# hot_plate_controller.net
KiCad netlist of a schematic drawn in EAGLE
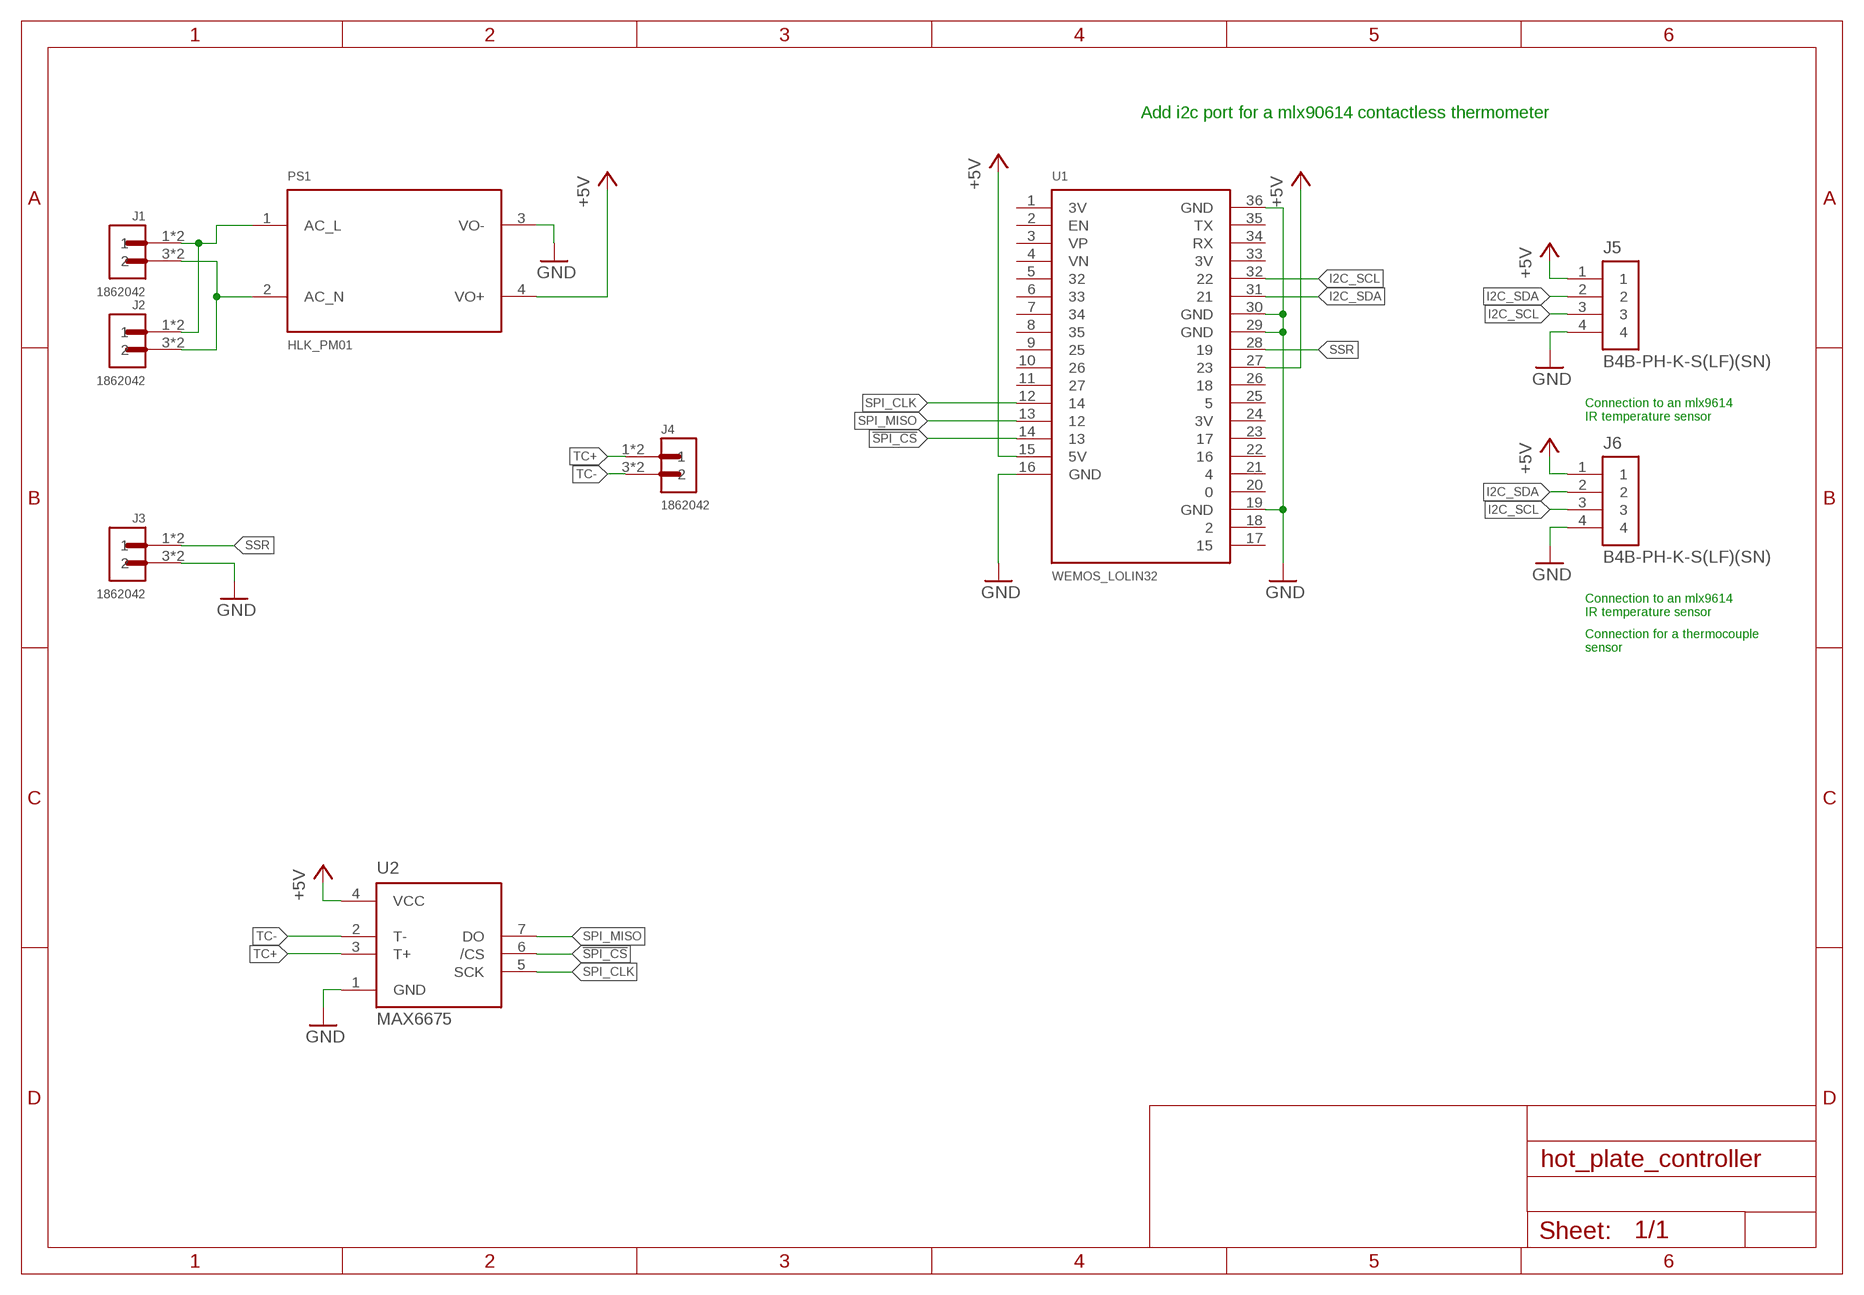
[diagram p0: schematic, sheet 1]

(export (version "E")
  (design (tool "Eeschema 10.0.6"))
  (components
    (comp (ref "J1")
      (value "1862042")
      (footprint "eagle-import:PHOENIX_1862042")
      (fields (field (name "MANUFACTURER") "Phoenix Contact"))
      (libsource (lib "eagle-import") (part "1862042"))
    )
    (comp (ref "J2")
      (value "1862042")
      (footprint "eagle-import:PHOENIX_1862042")
      (fields (field (name "MANUFACTURER") "Phoenix Contact"))
      (libsource (lib "eagle-import") (part "1862042"))
    )
    (comp (ref "J3")
      (value "1862042")
      (footprint "eagle-import:PHOENIX_1862042")
      (fields (field (name "MANUFACTURER") "Phoenix Contact"))
      (libsource (lib "eagle-import") (part "1862042"))
    )
    (comp (ref "J4")
      (value "1862042")
      (footprint "eagle-import:PHOENIX_1862042")
      (fields (field (name "MANUFACTURER") "Phoenix Contact"))
      (libsource (lib "eagle-import") (part "1862042"))
    )
    (comp (ref "J5")
      (value "B4B-PH-K-S(LF)(SN)")
      (footprint "eagle-import:JST_B4B-PH-K-S(LF)(SN)")
      (fields (field (name "MANUFACTURER") "JST"))
      (libsource (lib "eagle-import") (part "B4B-PH-K-S(LF)(SN)"))
    )
    (comp (ref "J6")
      (value "B4B-PH-K-S(LF)(SN)")
      (footprint "eagle-import:JST_B4B-PH-K-S(LF)(SN)")
      (fields (field (name "MANUFACTURER") "JST"))
      (libsource (lib "eagle-import") (part "B4B-PH-K-S(LF)(SN)"))
    )
    (comp (ref "PS1")
      (value "HLK_PM01")
      (footprint "eagle-import:HLK_PM")
      (libsource (lib "eagle-import") (part "HLK_PM01"))
    )
    (comp (ref "U1")
      (value "WEMOS_LOLIN32")
      (footprint "eagle-import:WEMOS_LOLIN32")
      (libsource (lib "eagle-import") (part "WEMOS_LOLIN32"))
    )
    (comp (ref "U2")
      (value "MAX6675")
      (footprint "eagle-import:SO08")
      (fields (field (name "MANUFACTURER") "Maxim Integrated"))
      (libsource (lib "eagle-import") (part "MAX6675"))
    )
  )
  (nets
    (net (code "1") (name "+5V") (class "Default")
      (node (ref "J5") (pin "1") (pinfunction "1_1") (pintype "passive"))
      (node (ref "J6") (pin "1") (pinfunction "1_1") (pintype "passive"))
      (node (ref "PS1") (pin "4") (pinfunction "VO+_4") (pintype "bidirectional"))
      (node (ref "U1") (pin "15") (pinfunction "5V_15") (pintype "bidirectional"))
      (node (ref "U1") (pin "27") (pinfunction "23_27") (pintype "bidirectional"))
      (node (ref "U2") (pin "4") (pinfunction "VCC_4") (pintype "power_in"))
    )
    (net (code "2") (name "/~{SPI_CS}") (class "Default")
      (node (ref "U1") (pin "14") (pinfunction "13_14") (pintype "bidirectional"))
      (node (ref "U2") (pin "6") (pinfunction "/CS_6") (pintype "input"))
    )
    (net (code "3") (name "GND") (class "Default")
      (node (ref "J3") (pin "3") (pinfunction "2_3") (pintype "passive"))
      (node (ref "J3") (pin "4") (pinfunction "2_4") (pintype "passive"))
      (node (ref "J5") (pin "4") (pinfunction "4_4") (pintype "passive"))
      (node (ref "J6") (pin "4") (pinfunction "4_4") (pintype "passive"))
      (node (ref "PS1") (pin "3") (pinfunction "VO-_3") (pintype "bidirectional"))
      (node (ref "U1") (pin "16") (pinfunction "GND_16") (pintype "bidirectional"))
      (node (ref "U1") (pin "19") (pinfunction "GND_19") (pintype "bidirectional"))
      (node (ref "U1") (pin "29") (pinfunction "GND_29") (pintype "bidirectional"))
      (node (ref "U1") (pin "30") (pinfunction "GND_30") (pintype "bidirectional"))
      (node (ref "U1") (pin "36") (pinfunction "GND_36") (pintype "bidirectional"))
      (node (ref "U2") (pin "1") (pinfunction "GND_1") (pintype "power_in"))
    )
    (net (code "4") (name "I2C_SCL") (class "Default")
      (node (ref "J5") (pin "3") (pinfunction "3_3") (pintype "passive"))
      (node (ref "J6") (pin "3") (pinfunction "3_3") (pintype "passive"))
      (node (ref "U1") (pin "32") (pinfunction "22_32") (pintype "bidirectional"))
    )
    (net (code "5") (name "I2C_SDA") (class "Default")
      (node (ref "J5") (pin "2") (pinfunction "2_2") (pintype "passive"))
      (node (ref "J6") (pin "2") (pinfunction "2_2") (pintype "passive"))
      (node (ref "U1") (pin "31") (pinfunction "21_31") (pintype "bidirectional"))
    )
    (net (code "6") (name "Net-(PS1-AC_L)") (class "Default")
      (node (ref "J1") (pin "1") (pinfunction "1_1") (pintype "passive"))
      (node (ref "J1") (pin "2") (pinfunction "1_2") (pintype "passive"))
      (node (ref "J2") (pin "1") (pinfunction "1_1") (pintype "passive"))
      (node (ref "J2") (pin "2") (pinfunction "1_2") (pintype "passive"))
      (node (ref "PS1") (pin "1") (pinfunction "AC_L_1") (pintype "bidirectional"))
    )
    (net (code "7") (name "Net-(PS1-AC_N)") (class "Default")
      (node (ref "J1") (pin "3") (pinfunction "2_3") (pintype "passive"))
      (node (ref "J1") (pin "4") (pinfunction "2_4") (pintype "passive"))
      (node (ref "J2") (pin "3") (pinfunction "2_3") (pintype "passive"))
      (node (ref "J2") (pin "4") (pinfunction "2_4") (pintype "passive"))
      (node (ref "PS1") (pin "2") (pinfunction "AC_N_2") (pintype "bidirectional"))
    )
    (net (code "8") (name "SPI_CLK") (class "Default")
      (node (ref "U1") (pin "12") (pinfunction "14_12") (pintype "bidirectional"))
      (node (ref "U2") (pin "5") (pinfunction "SCK_5") (pintype "input"))
    )
    (net (code "9") (name "SPI_MISO") (class "Default")
      (node (ref "U1") (pin "13") (pinfunction "12_13") (pintype "bidirectional"))
      (node (ref "U2") (pin "7") (pinfunction "DO_7") (pintype "output"))
    )
    (net (code "10") (name "SSR") (class "Default")
      (node (ref "J3") (pin "1") (pinfunction "1_1") (pintype "passive"))
      (node (ref "J3") (pin "2") (pinfunction "1_2") (pintype "passive"))
      (node (ref "U1") (pin "28") (pinfunction "19_28") (pintype "bidirectional"))
    )
    (net (code "11") (name "TC+") (class "Default")
      (node (ref "J4") (pin "1") (pinfunction "1_1") (pintype "passive"))
      (node (ref "J4") (pin "2") (pinfunction "1_2") (pintype "passive"))
      (node (ref "U2") (pin "3") (pinfunction "T+_3") (pintype "input"))
    )
    (net (code "12") (name "TC-") (class "Default")
      (node (ref "J4") (pin "3") (pinfunction "2_3") (pintype "passive"))
      (node (ref "J4") (pin "4") (pinfunction "2_4") (pintype "passive"))
      (node (ref "U2") (pin "2") (pinfunction "T-_2") (pintype "input"))
    )
    (net (code "13") (name "unconnected-(U1-0-Pad20)") (class "Default")
      (node (ref "U1") (pin "20") (pinfunction "0_20") (pintype "bidirectional"))
    )
    (net (code "14") (name "unconnected-(U1-2-Pad18)") (class "Default")
      (node (ref "U1") (pin "18") (pinfunction "2_18") (pintype "bidirectional"))
    )
    (net (code "15") (name "unconnected-(U1-3V-Pad1)") (class "Default")
      (node (ref "U1") (pin "1") (pinfunction "3V_1") (pintype "bidirectional"))
    )
    (net (code "16") (name "unconnected-(U1-3V-Pad24)") (class "Default")
      (node (ref "U1") (pin "24") (pinfunction "3V_24") (pintype "bidirectional"))
    )
    (net (code "17") (name "unconnected-(U1-3V-Pad33)") (class "Default")
      (node (ref "U1") (pin "33") (pinfunction "3V_33") (pintype "bidirectional"))
    )
    (net (code "18") (name "unconnected-(U1-4-Pad21)") (class "Default")
      (node (ref "U1") (pin "21") (pinfunction "4_21") (pintype "bidirectional"))
    )
    (net (code "19") (name "unconnected-(U1-5-Pad25)") (class "Default")
      (node (ref "U1") (pin "25") (pinfunction "5_25") (pintype "bidirectional"))
    )
    (net (code "20") (name "unconnected-(U1-15-Pad17)") (class "Default")
      (node (ref "U1") (pin "17") (pinfunction "15_17") (pintype "bidirectional"))
    )
    (net (code "21") (name "unconnected-(U1-16-Pad22)") (class "Default")
      (node (ref "U1") (pin "22") (pinfunction "16_22") (pintype "bidirectional"))
    )
    (net (code "22") (name "unconnected-(U1-17-Pad23)") (class "Default")
      (node (ref "U1") (pin "23") (pinfunction "17_23") (pintype "bidirectional"))
    )
    (net (code "23") (name "unconnected-(U1-18-Pad26)") (class "Default")
      (node (ref "U1") (pin "26") (pinfunction "18_26") (pintype "bidirectional"))
    )
    (net (code "24") (name "unconnected-(U1-25-Pad9)") (class "Default")
      (node (ref "U1") (pin "9") (pinfunction "25_9") (pintype "bidirectional"))
    )
    (net (code "25") (name "unconnected-(U1-26-Pad10)") (class "Default")
      (node (ref "U1") (pin "10") (pinfunction "26_10") (pintype "bidirectional"))
    )
    (net (code "26") (name "unconnected-(U1-27-Pad11)") (class "Default")
      (node (ref "U1") (pin "11") (pinfunction "27_11") (pintype "bidirectional"))
    )
    (net (code "27") (name "unconnected-(U1-32-Pad5)") (class "Default")
      (node (ref "U1") (pin "5") (pinfunction "32_5") (pintype "bidirectional"))
    )
    (net (code "28") (name "unconnected-(U1-33-Pad6)") (class "Default")
      (node (ref "U1") (pin "6") (pinfunction "33_6") (pintype "bidirectional"))
    )
    (net (code "29") (name "unconnected-(U1-34-Pad7)") (class "Default")
      (node (ref "U1") (pin "7") (pinfunction "34_7") (pintype "bidirectional"))
    )
    (net (code "30") (name "unconnected-(U1-35-Pad8)") (class "Default")
      (node (ref "U1") (pin "8") (pinfunction "35_8") (pintype "bidirectional"))
    )
    (net (code "31") (name "unconnected-(U1-EN-Pad2)") (class "Default")
      (node (ref "U1") (pin "2") (pinfunction "EN_2") (pintype "bidirectional"))
    )
    (net (code "32") (name "unconnected-(U1-RX-Pad34)") (class "Default")
      (node (ref "U1") (pin "34") (pinfunction "RX_34") (pintype "bidirectional"))
    )
    (net (code "33") (name "unconnected-(U1-TX-Pad35)") (class "Default")
      (node (ref "U1") (pin "35") (pinfunction "TX_35") (pintype "bidirectional"))
    )
    (net (code "34") (name "unconnected-(U1-VN-Pad4)") (class "Default")
      (node (ref "U1") (pin "4") (pinfunction "VN_4") (pintype "bidirectional"))
    )
    (net (code "35") (name "unconnected-(U1-VP-Pad3)") (class "Default")
      (node (ref "U1") (pin "3") (pinfunction "VP_3") (pintype "bidirectional"))
    )
  )
)
